# Power_ToSimple.net
KiCad netlist of a schematic drawn in EAGLE
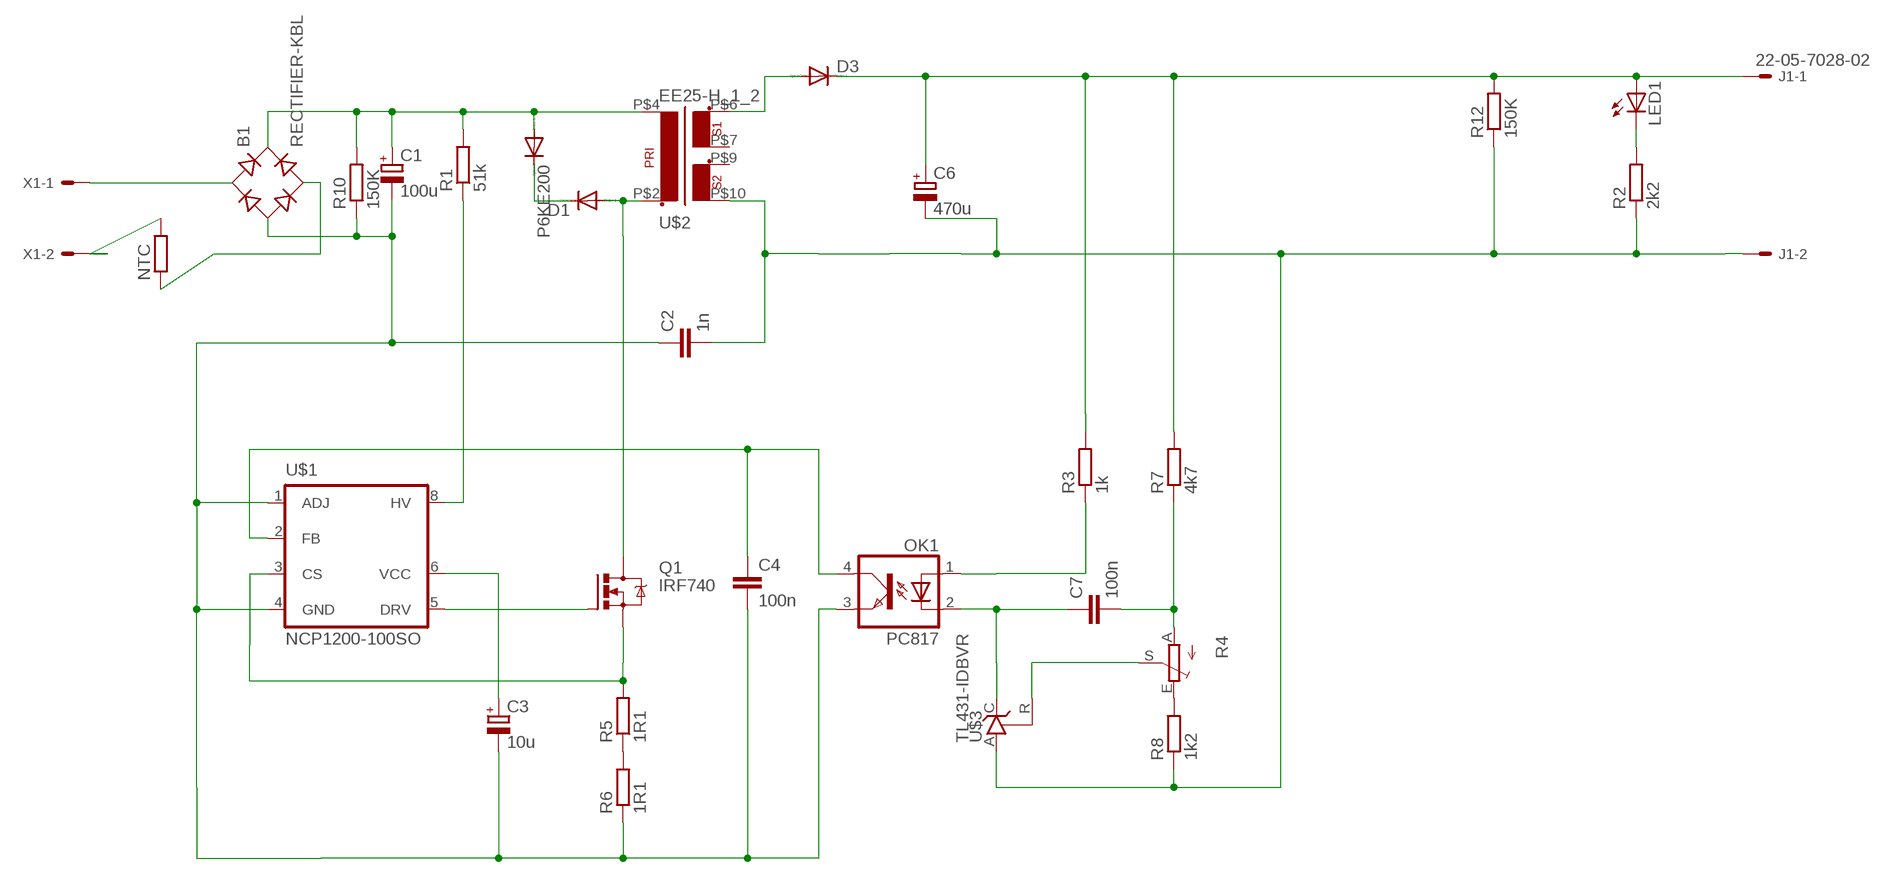
[diagram p0: schematic, sheet 1]

(export (version "E")
  (design (tool "Eeschema 10.0.6"))
  (components
    (comp (ref "B1")
      (value "RECTIFIER-KBL")
      (footprint "eagle-import:KBL")
      (libsource (lib "eagle-import") (part "RECTIFIER-KBL"))
    )
    (comp (ref "C1")
      (value "100u")
      (footprint "eagle-import:EB22,5D")
      (libsource (lib "eagle-import") (part "CPOL-EUE10-22.5"))
    )
    (comp (ref "C2")
      (value "1n")
      (footprint "eagle-import:C050-024X044")
      (libsource (lib "eagle-import") (part "C-EU050-024X044"))
    )
    (comp (ref "C3")
      (value "10u")
      (footprint "eagle-import:E2,5-5")
      (libsource (lib "eagle-import") (part "CPOL-EUE2.5-5"))
    )
    (comp (ref "C4")
      (value "100n")
      (footprint "eagle-import:C1206")
      (libsource (lib "eagle-import") (part "C-EUC1206"))
    )
    (comp (ref "C6")
      (value "470u")
      (footprint "eagle-import:E5-10,5")
      (libsource (lib "eagle-import") (part "CPOL-EUE5-10.5"))
    )
    (comp (ref "C7")
      (value "100n")
      (footprint "eagle-import:C1206")
      (libsource (lib "eagle-import") (part "C-EUC1206"))
    )
    (comp (ref "D1")
      (value "DIODE-DO-214AC")
      (footprint "eagle-import:DO-214AC")
      (libsource (lib "eagle-import") (part "DIODE-DO-214AC"))
    )
    (comp (ref "D3")
      (value "DIODE-DO-214AC")
      (footprint "eagle-import:DO-214AC")
      (libsource (lib "eagle-import") (part "DIODE-DO-214AC"))
    )
    (comp (ref "J1")
      (value "22-05-7028-02")
      (footprint "eagle-import:7395-02")
      (libsource (lib "eagle-import") (part "22-?-0205-7028"))
    )
    (comp (ref "LED1")
      (value "LED5MM")
      (footprint "eagle-import:LED5MM")
      (libsource (lib "eagle-import") (part "LED5MM"))
    )
    (comp (ref "NTC")
      (value "R-EU_0207/10")
      (footprint "eagle-import:0207_10")
      (libsource (lib "eagle-import") (part "R-EU_0207/10"))
    )
    (comp (ref "OK1")
      (value "PC817")
      (footprint "eagle-import:DIL04")
      (fields (field (name "MPN") "PC817X4J000F"))
      (libsource (lib "eagle-import") (part "PC817"))
    )
    (comp (ref "P6KE200")
      (value "DIODE-DO15-12")
      (footprint "eagle-import:DO15-12")
      (libsource (lib "eagle-import") (part "DIODE-DO15-12"))
    )
    (comp (ref "Q1")
      (value "IRF740")
      (footprint "eagle-import:TO220BV")
      (libsource (lib "eagle-import") (part "IRF740"))
    )
    (comp (ref "R1")
      (value "51k")
      (footprint "eagle-import:0922_22")
      (libsource (lib "eagle-import") (part "R-EU_0922/22"))
    )
    (comp (ref "R2")
      (value "2k2")
      (footprint "eagle-import:R1206")
      (libsource (lib "eagle-import") (part "R-EU_R1206"))
    )
    (comp (ref "R3")
      (value "1k")
      (footprint "eagle-import:R1206")
      (libsource (lib "eagle-import") (part "R-EU_R1206"))
    )
    (comp (ref "R4")
      (value "TRIM_EU-S75H")
      (footprint "eagle-import:S75H")
      (libsource (lib "eagle-import") (part "TRIM_EU-S75H"))
    )
    (comp (ref "R5")
      (value "1R1")
      (footprint "eagle-import:R1206")
      (libsource (lib "eagle-import") (part "R-EU_R1206"))
    )
    (comp (ref "R6")
      (value "1R1")
      (footprint "eagle-import:R1206")
      (libsource (lib "eagle-import") (part "R-EU_R1206"))
    )
    (comp (ref "R7")
      (value "4k7")
      (footprint "eagle-import:R1206")
      (libsource (lib "eagle-import") (part "R-EU_R1206"))
    )
    (comp (ref "R8")
      (value "1k2")
      (footprint "eagle-import:R1206")
      (libsource (lib "eagle-import") (part "R-EU_R1206"))
    )
    (comp (ref "R10")
      (value "150K")
      (footprint "eagle-import:R1206")
      (libsource (lib "eagle-import") (part "R-EU_R1206"))
    )
    (comp (ref "R12")
      (value "150K")
      (footprint "eagle-import:R1206")
      (libsource (lib "eagle-import") (part "R-EU_R1206"))
    )
    (comp (ref "U$1")
      (value "NCP1200-100SO")
      (footprint "eagle-import:SOP8")
      (libsource (lib "eagle-import") (part "NCP1200-100SO"))
    )
    (comp (ref "U$2")
      (value "EE25-H_1_2")
      (footprint "eagle-import:EE25")
      (libsource (lib "eagle-import") (part "EE25-H_1_2"))
    )
    (comp (ref "U$3")
      (value "TL431-IDBVR")
      (footprint "eagle-import:SOT23-5")
      (libsource (lib "eagle-import") (part "TL431-IDBVR"))
    )
    (comp (ref "X1")
      (value "KK-156-2")
      (footprint "eagle-import:KK-156-2")
      (libsource (lib "eagle-import") (part "KK-156-2"))
    )
  )
  (nets
    (net (code "1") (name "Net-(B1-PadAC2)") (class "Default")
      (node (ref "B1") (pin "AC2") (pinfunction "AC2_AC2") (pintype "passive"))
      (node (ref "NTC") (pin "1") (pinfunction "1_1") (pintype "passive"))
    )
    (net (code "2") (name "Net-(C7-Pad2)") (class "Default")
      (node (ref "C7") (pin "2") (pinfunction "2_2") (pintype "passive"))
      (node (ref "R4") (pin "A") (pinfunction "A_A") (pintype "passive"))
      (node (ref "R7") (pin "1") (pinfunction "1_1") (pintype "passive"))
    )
    (net (code "3") (name "Net-(D1-PadC)") (class "Default")
      (node (ref "D1") (pin "C") (pinfunction "C_C") (pintype "passive"))
      (node (ref "P6KE200") (pin "C") (pinfunction "C_C") (pintype "passive"))
    )
    (net (code "4") (name "Net-(J1A-S)") (class "Default")
      (node (ref "C6") (pin "+") (pinfunction "+_+") (pintype "passive"))
      (node (ref "D3") (pin "C") (pinfunction "C_C") (pintype "passive"))
      (node (ref "J1") (pin "1") (pinfunction "S_1") (pintype "passive"))
      (node (ref "LED1") (pin "A") (pinfunction "A_A") (pintype "passive"))
      (node (ref "R12") (pin "2") (pinfunction "2_2") (pintype "passive"))
      (node (ref "R3") (pin "2") (pinfunction "2_2") (pintype "passive"))
      (node (ref "R7") (pin "2") (pinfunction "2_2") (pintype "passive"))
    )
    (net (code "5") (name "Net-(J1B-S)") (class "Default")
      (node (ref "C2") (pin "2") (pinfunction "2_2") (pintype "passive"))
      (node (ref "C6") (pin "-") (pinfunction "-_-") (pintype "passive"))
      (node (ref "J1") (pin "2") (pinfunction "S_2") (pintype "passive"))
      (node (ref "R12") (pin "1") (pinfunction "1_1") (pintype "passive"))
      (node (ref "R2") (pin "1") (pinfunction "1_1") (pintype "passive"))
      (node (ref "R8") (pin "1") (pinfunction "1_1") (pintype "passive"))
      (node (ref "U$2") (pin "P$10") (pinfunction "6_P$10") (pintype "passive"))
      (node (ref "U$3") (pin "A") (pinfunction "A_A") (pintype "passive"))
    )
    (net (code "6") (name "Net-(LED1-C)") (class "Default")
      (node (ref "LED1") (pin "K") (pinfunction "C_K") (pintype "passive"))
      (node (ref "R2") (pin "2") (pinfunction "2_2") (pintype "passive"))
    )
    (net (code "7") (name "Net-(OK1-A)") (class "Default")
      (node (ref "OK1") (pin "1") (pinfunction "A_1") (pintype "passive"))
      (node (ref "R3") (pin "1") (pinfunction "1_1") (pintype "passive"))
    )
    (net (code "8") (name "Net-(OK1-C)") (class "Default")
      (node (ref "C7") (pin "1") (pinfunction "1_1") (pintype "passive"))
      (node (ref "OK1") (pin "2") (pinfunction "C_2") (pintype "passive"))
      (node (ref "U$3") (pin "C") (pinfunction "C_C") (pintype "passive"))
    )
    (net (code "9") (name "Net-(OK1-COL)") (class "Default")
      (node (ref "C4") (pin "1") (pinfunction "1_1") (pintype "passive"))
      (node (ref "OK1") (pin "4") (pinfunction "COL_4") (pintype "passive"))
      (node (ref "U$1") (pin "2") (pinfunction "FB_2") (pintype "input"))
    )
    (net (code "10") (name "Net-(OK1-EMIT)") (class "Default")
      (node (ref "B1") (pin "-") (pinfunction "-_-") (pintype "passive"))
      (node (ref "C1") (pin "-") (pinfunction "-_-") (pintype "passive"))
      (node (ref "C2") (pin "1") (pinfunction "1_1") (pintype "passive"))
      (node (ref "C3") (pin "-") (pinfunction "-_-") (pintype "passive"))
      (node (ref "C4") (pin "2") (pinfunction "2_2") (pintype "passive"))
      (node (ref "OK1") (pin "3") (pinfunction "EMIT_3") (pintype "passive"))
      (node (ref "R10") (pin "1") (pinfunction "1_1") (pintype "passive"))
      (node (ref "R6") (pin "1") (pinfunction "1_1") (pintype "passive"))
      (node (ref "U$1") (pin "1") (pinfunction "ADJ_1") (pintype "passive"))
      (node (ref "U$1") (pin "4") (pinfunction "GND_4") (pintype "passive"))
    )
    (net (code "11") (name "Net-(R4-PadE)") (class "Default")
      (node (ref "R4") (pin "E") (pinfunction "E_E") (pintype "passive"))
      (node (ref "R8") (pin "2") (pinfunction "2_2") (pintype "passive"))
    )
    (net (code "12") (name "Net-(R4-PadS)") (class "Default")
      (node (ref "R4") (pin "S") (pinfunction "S_S") (pintype "passive"))
      (node (ref "U$3") (pin "R") (pinfunction "R_R") (pintype "passive"))
    )
    (net (code "13") (name "Net-(R5-Pad1)") (class "Default")
      (node (ref "R5") (pin "1") (pinfunction "1_1") (pintype "passive"))
      (node (ref "R6") (pin "2") (pinfunction "2_2") (pintype "passive"))
    )
    (net (code "14") (name "Net-(U$1-CS)") (class "Default")
      (node (ref "Q1") (pin "S") (pinfunction "S_S") (pintype "passive"))
      (node (ref "R5") (pin "2") (pinfunction "2_2") (pintype "passive"))
      (node (ref "U$1") (pin "3") (pinfunction "CS_3") (pintype "input"))
    )
    (net (code "15") (name "Net-(U$1-DRV)") (class "Default")
      (node (ref "Q1") (pin "G") (pinfunction "G_G") (pintype "passive"))
      (node (ref "U$1") (pin "5") (pinfunction "DRV_5") (pintype "power_in"))
    )
    (net (code "16") (name "Net-(U$1-HV)") (class "Default")
      (node (ref "R1") (pin "1") (pinfunction "1_1") (pintype "passive"))
      (node (ref "U$1") (pin "8") (pinfunction "HV_8") (pintype "passive"))
    )
    (net (code "17") (name "Net-(U$1-VCC)") (class "Default")
      (node (ref "C3") (pin "+") (pinfunction "+_+") (pintype "passive"))
      (node (ref "U$1") (pin "6") (pinfunction "VCC_6") (pintype "output"))
    )
    (net (code "18") (name "Net-(U$2-1)") (class "Default")
      (node (ref "D1") (pin "A") (pinfunction "A_A") (pintype "passive"))
      (node (ref "Q1") (pin "D") (pinfunction "D_D") (pintype "passive"))
      (node (ref "U$2") (pin "P$2") (pinfunction "1_P$2") (pintype "passive"))
    )
    (net (code "19") (name "Net-(U$2-2)") (class "Default")
      (node (ref "B1") (pin "+") (pinfunction "+_+") (pintype "passive"))
      (node (ref "C1") (pin "+") (pinfunction "+_+") (pintype "passive"))
      (node (ref "P6KE200") (pin "A") (pinfunction "A_A") (pintype "passive"))
      (node (ref "R1") (pin "2") (pinfunction "2_2") (pintype "passive"))
      (node (ref "R10") (pin "2") (pinfunction "2_2") (pintype "passive"))
      (node (ref "U$2") (pin "P$4") (pinfunction "2_P$4") (pintype "passive"))
    )
    (net (code "20") (name "Net-(U$2-3)") (class "Default")
      (node (ref "D3") (pin "A") (pinfunction "A_A") (pintype "passive"))
      (node (ref "U$2") (pin "P$6") (pinfunction "3_P$6") (pintype "passive"))
    )
    (net (code "21") (name "Net-(X1A-S)") (class "Default")
      (node (ref "B1") (pin "AC1") (pinfunction "AC1_AC1") (pintype "passive"))
      (node (ref "X1") (pin "1") (pinfunction "S_1") (pintype "passive"))
    )
    (net (code "22") (name "Net-(X1B-S)") (class "Default")
      (node (ref "NTC") (pin "2") (pinfunction "2_2") (pintype "passive"))
      (node (ref "X1") (pin "2") (pinfunction "S_2") (pintype "passive"))
    )
    (net (code "23") (name "unconnected-(U$2-4-PadP$7)") (class "Default")
      (node (ref "U$2") (pin "P$7") (pinfunction "4_P$7") (pintype "passive"))
    )
    (net (code "24") (name "unconnected-(U$2-5-PadP$9)") (class "Default")
      (node (ref "U$2") (pin "P$9") (pinfunction "5_P$9") (pintype "passive"))
    )
  )
)
